# power_ic.net
KiCad netlist of a schematic drawn in Altium Designer
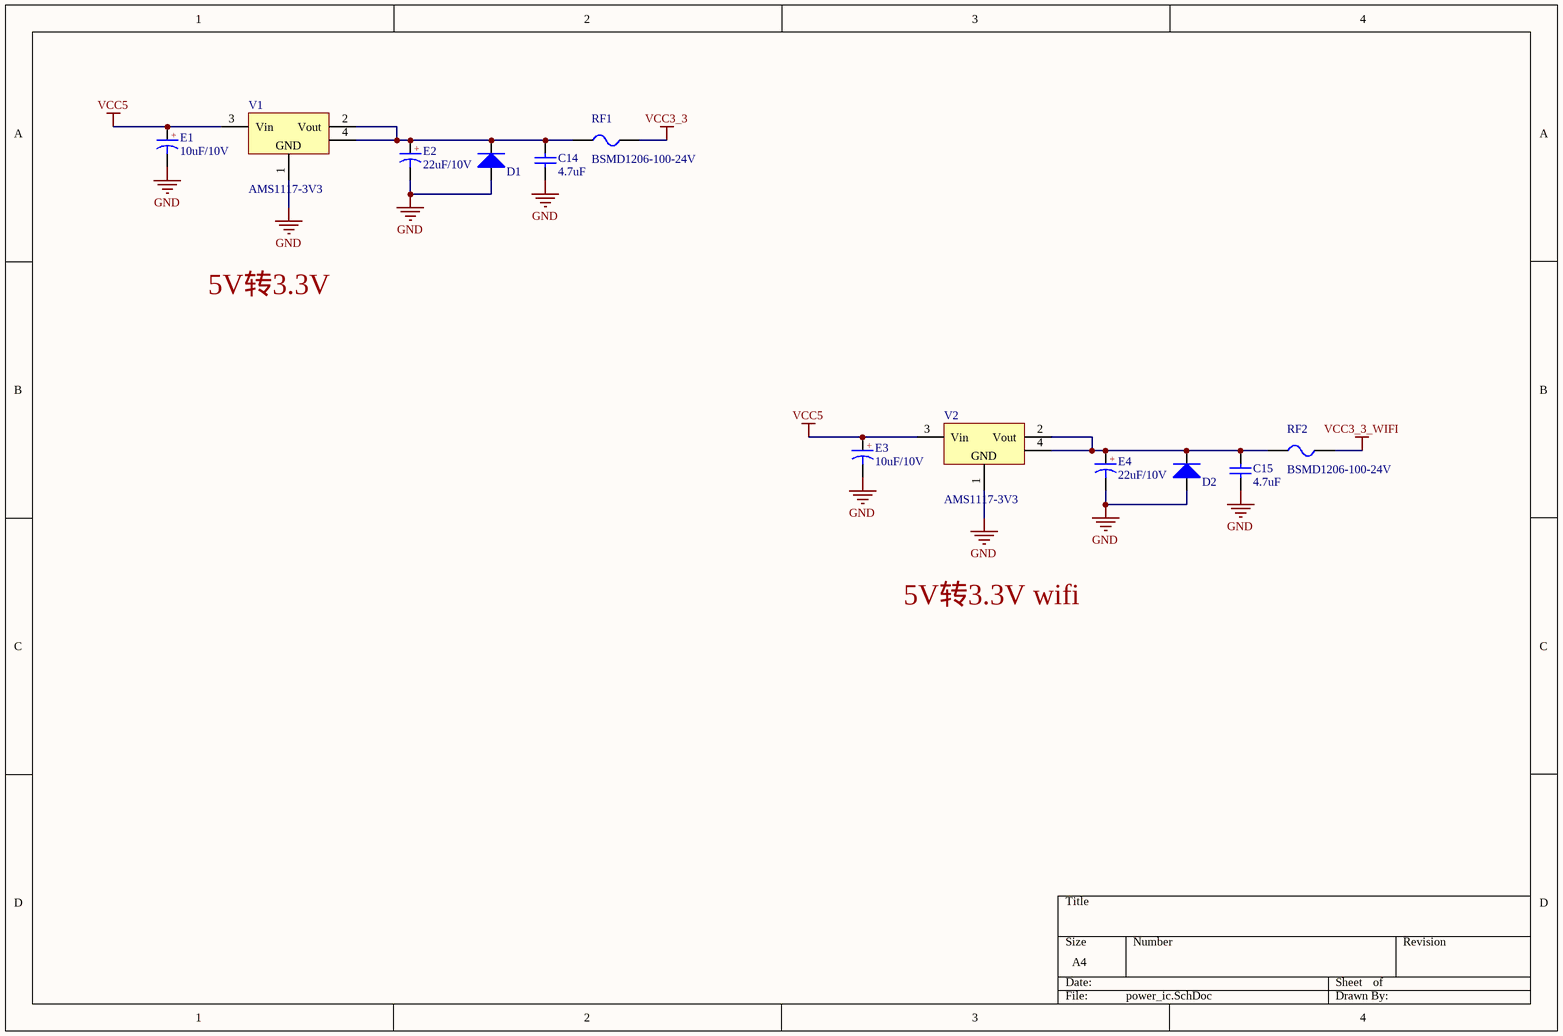
[diagram p0: power_ic.SchDoc]

(export (version "E")
  (design (tool "Eeschema 10.0.6"))
  (components
    (comp (ref "C14")
      (value "4.7uF")
      (footprint "C0603_M")
      (description "贴片电容/MLCC电容")
      (libsource (lib "0.1 - 电阻-电容-电感-保险丝-晶振-晶体-磁珠-电位器-法拉电容-馈通电容") (part "C"))
    )
    (comp (ref "C15")
      (value "4.7uF")
      (footprint "C0603_M")
      (description "贴片电容/MLCC电容")
      (libsource (lib "0.1 - 电阻-电容-电感-保险丝-晶振-晶体-磁珠-电位器-法拉电容-馈通电容") (part "C"))
    )
    (comp (ref "D1")
      (value "UDD32C03L01")
      (footprint "SOD-323")
      (description "TVS通用 C78439")
      (libsource (lib "0.2 - 二极管-TVS-ESD-整流桥-放电管") (part "TVS"))
    )
    (comp (ref "D2")
      (value "UDD32C03L01")
      (footprint "SOD-323")
      (description "TVS通用 C78439")
      (libsource (lib "0.2 - 二极管-TVS-ESD-整流桥-放电管") (part "TVS"))
    )
    (comp (ref "E1")
      (value "10uF/10V")
      (footprint "C_3216")
      (description "贴片钽电容 C7171")
      (libsource (lib "0.1 - 电阻-电容-电感-保险丝-晶振-晶体-磁珠-电位器-法拉电容-馈通电容") (part "CT"))
    )
    (comp (ref "E2")
      (value "22uF/10V")
      (footprint "C_3216")
      (description "贴片钽电容  C11366")
      (libsource (lib "0.1 - 电阻-电容-电感-保险丝-晶振-晶体-磁珠-电位器-法拉电容-馈通电容") (part "CT"))
    )
    (comp (ref "E3")
      (value "10uF/10V")
      (footprint "C_3216")
      (description "贴片钽电容 C7171")
      (libsource (lib "0.1 - 电阻-电容-电感-保险丝-晶振-晶体-磁珠-电位器-法拉电容-馈通电容") (part "CT"))
    )
    (comp (ref "E4")
      (value "22uF/10V")
      (footprint "C_3216")
      (description "贴片钽电容  C11366")
      (libsource (lib "0.1 - 电阻-电容-电感-保险丝-晶振-晶体-磁珠-电位器-法拉电容-馈通电容") (part "CT"))
    )
    (comp (ref "RF1")
      (value "BSMD1206-100-24V")
      (footprint "F1206")
      (description "PPTC自恢复保险丝 C910830")
      (libsource (lib "0.1 - 电阻-电容-电感-保险丝-晶振-晶体-磁珠-电位器-法拉电容-馈通电容") (part "FUSE-PPTC"))
    )
    (comp (ref "RF2")
      (value "BSMD1206-100-24V")
      (footprint "F1206")
      (description "PPTC自恢复保险丝 C910830")
      (libsource (lib "0.1 - 电阻-电容-电感-保险丝-晶振-晶体-磁珠-电位器-法拉电容-馈通电容") (part "FUSE-PPTC"))
    )
    (comp (ref "V1")
      (value "AMS1117-3V3")
      (footprint "SOT223_L")
      (description "三端稳压芯片")
      (libsource (lib "0.7 - 电源类芯片") (part "AMS1117"))
    )
    (comp (ref "V2")
      (value "AMS1117-3V3")
      (footprint "SOT223_L")
      (description "三端稳压芯片")
      (libsource (lib "0.7 - 电源类芯片") (part "AMS1117"))
    )
  )
  (nets
    (net (code "1") (name "GND") (class "Default")
      (node (ref "C14") (pin "2") (pinfunction "2_2") (pintype "passive"))
      (node (ref "C15") (pin "2") (pinfunction "2_2") (pintype "passive"))
      (node (ref "D1") (pin "1") (pinfunction "A_1") (pintype "passive"))
      (node (ref "D2") (pin "1") (pinfunction "A_1") (pintype "passive"))
      (node (ref "E1") (pin "2") (pinfunction "K_2") (pintype "passive"))
      (node (ref "E2") (pin "2") (pinfunction "K_2") (pintype "passive"))
      (node (ref "E3") (pin "2") (pinfunction "K_2") (pintype "passive"))
      (node (ref "E4") (pin "2") (pinfunction "K_2") (pintype "passive"))
      (node (ref "V1") (pin "1") (pinfunction "GND_1") (pintype "passive"))
      (node (ref "V2") (pin "1") (pinfunction "GND_1") (pintype "passive"))
    )
    (net (code "2") (name "Net-(D1-K)") (class "Default")
      (node (ref "C14") (pin "1") (pinfunction "1_1") (pintype "passive"))
      (node (ref "D1") (pin "2") (pinfunction "K_2") (pintype "passive"))
      (node (ref "E2") (pin "1") (pinfunction "A_1") (pintype "passive"))
      (node (ref "RF1") (pin "2") (pinfunction "2_2") (pintype "passive"))
      (node (ref "V1") (pin "2") (pinfunction "Vout_2") (pintype "passive"))
      (node (ref "V1") (pin "4") (pinfunction "GND_4") (pintype "passive"))
    )
    (net (code "3") (name "Net-(D2-K)") (class "Default")
      (node (ref "C15") (pin "1") (pinfunction "1_1") (pintype "passive"))
      (node (ref "D2") (pin "2") (pinfunction "K_2") (pintype "passive"))
      (node (ref "E4") (pin "1") (pinfunction "A_1") (pintype "passive"))
      (node (ref "RF2") (pin "2") (pinfunction "2_2") (pintype "passive"))
      (node (ref "V2") (pin "2") (pinfunction "Vout_2") (pintype "passive"))
      (node (ref "V2") (pin "4") (pinfunction "GND_4") (pintype "passive"))
    )
    (net (code "4") (name "VCC3_3") (class "Default")
      (node (ref "RF1") (pin "1") (pinfunction "1_1") (pintype "passive"))
    )
    (net (code "5") (name "VCC3_3_WIFI") (class "Default")
      (node (ref "RF2") (pin "1") (pinfunction "1_1") (pintype "passive"))
    )
    (net (code "6") (name "VCC5") (class "Default")
      (node (ref "E1") (pin "1") (pinfunction "A_1") (pintype "passive"))
      (node (ref "E3") (pin "1") (pinfunction "A_1") (pintype "passive"))
      (node (ref "V1") (pin "3") (pinfunction "Vin_3") (pintype "passive"))
      (node (ref "V2") (pin "3") (pinfunction "Vin_3") (pintype "passive"))
    )
  )
)
